# adapter_rev1_tt.net
KiCad netlist of a schematic drawn in Altium Designer
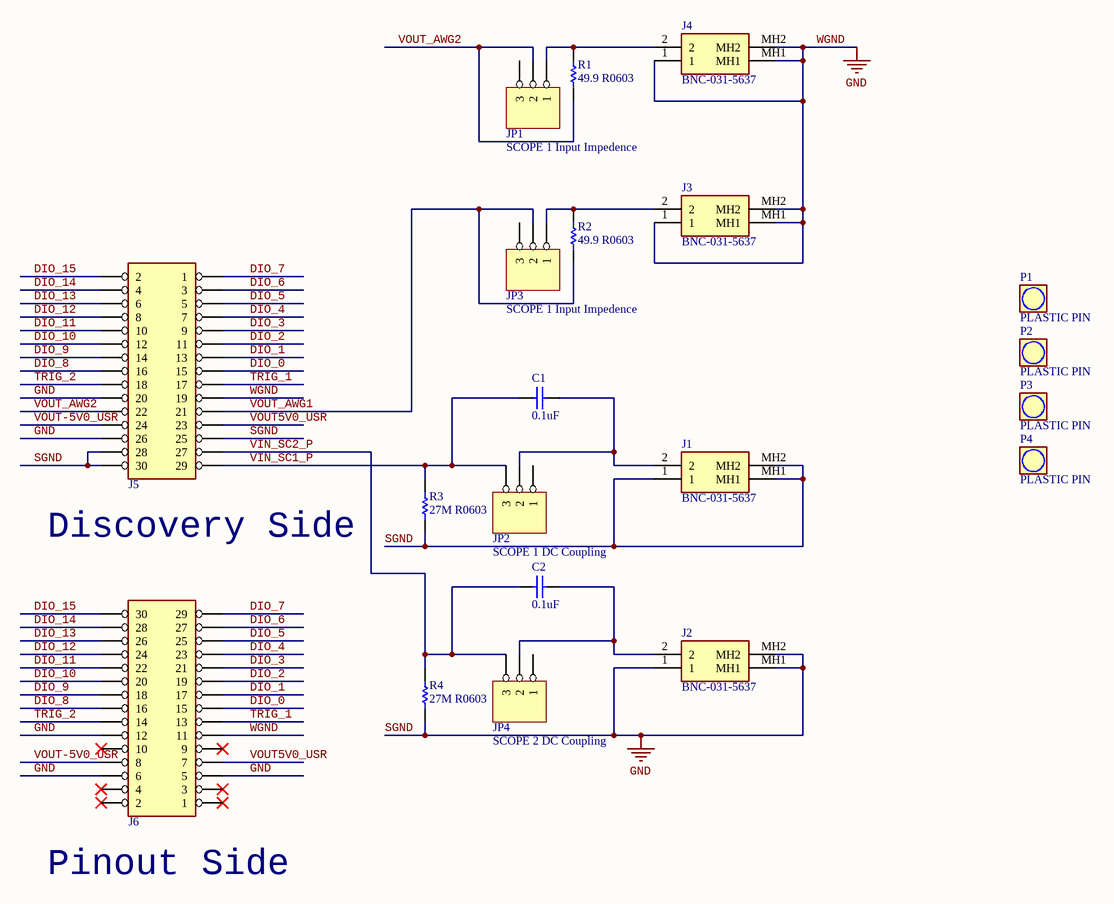
[diagram p0: adapter_rev1_tt.SchDoc]

(export (version "E")
  (design (tool "Eeschema 10.0.6"))
  (components
    (comp (ref "C1")
      (value "0.1uF")
      (footprint "0603_C")
      (description "Capacitor")
      (fields (field (name "PUBLISHER") "Altium Limited"))
      (libsource (lib "My Footprint") (part "CAP"))
    )
    (comp (ref "C2")
      (value "0.1uF")
      (footprint "0603_C")
      (description "Capacitor")
      (fields (field (name "PUBLISHER") "Altium Limited"))
      (libsource (lib "My Footprint") (part "CAP"))
    )
    (comp (ref "J1")
      (value "BNC-031-5637")
      (footprint "0315637")
      (description "Connector")
      (fields
        (field (name "MANUFACTURER_PART_NUMBER") "031-5637")
        (field (name "MOUSER PART NUMBER") "523-31-5637")
      )
      (libsource (lib "My Footprint") (part "BNC-031-5637"))
    )
    (comp (ref "J2")
      (value "BNC-031-5637")
      (footprint "0315637")
      (description "Connector")
      (fields
        (field (name "MANUFACTURER_PART_NUMBER") "031-5637")
        (field (name "MOUSER PART NUMBER") "523-31-5637")
      )
      (libsource (lib "My Footprint") (part "BNC-031-5637"))
    )
    (comp (ref "J3")
      (value "BNC-031-5637")
      (footprint "0315637")
      (description "Connector")
      (fields
        (field (name "MANUFACTURER_PART_NUMBER") "031-5637")
        (field (name "MOUSER PART NUMBER") "523-31-5637")
      )
      (libsource (lib "My Footprint") (part "BNC-031-5637"))
    )
    (comp (ref "J4")
      (value "BNC-031-5637")
      (footprint "0315637")
      (description "Connector")
      (fields
        (field (name "MANUFACTURER_PART_NUMBER") "031-5637")
        (field (name "MOUSER PART NUMBER") "523-31-5637")
      )
      (libsource (lib "My Footprint") (part "BNC-031-5637"))
    )
    (comp (ref "J5")
      (value "HEADER 15x2")
      (footprint "HEADER15X2_CE")
      (libsource (lib "My Footprint") (part "HEADER 15x2"))
    )
    (comp (ref "J6")
      (value "HEADER 15x2")
      (footprint "HEADER15X2_CE")
      (libsource (lib "") (part "HEADER 15x2_1"))
    )
    (comp (ref "JP1")
      (value "SCOPE 1 Input Impedence")
      (footprint "header3")
      (libsource (lib "My Footprint") (part "HEADER 3"))
    )
    (comp (ref "JP2")
      (value "SCOPE 1 DC Coupling")
      (footprint "header3")
      (libsource (lib "My Footprint") (part "HEADER 3"))
    )
    (comp (ref "JP3")
      (value "SCOPE 1 Input Impedence")
      (footprint "header3")
      (libsource (lib "My Footprint") (part "HEADER 3"))
    )
    (comp (ref "JP4")
      (value "SCOPE 2 DC Coupling")
      (footprint "header3")
      (libsource (lib "My Footprint") (part "HEADER 3"))
    )
    (comp (ref "P1")
      (value "PLASTIC PIN")
      (footprint "PLASTIC_PIN")
      (libsource (lib "My Footprint") (part "PLASTIC_PIN"))
    )
    (comp (ref "P2")
      (value "PLASTIC PIN")
      (footprint "PLASTIC_PIN")
      (libsource (lib "My Footprint") (part "PLASTIC_PIN"))
    )
    (comp (ref "P3")
      (value "PLASTIC PIN")
      (footprint "PLASTIC_PIN")
      (libsource (lib "My Footprint") (part "PLASTIC_PIN"))
    )
    (comp (ref "P4")
      (value "PLASTIC PIN")
      (footprint "PLASTIC_PIN")
      (libsource (lib "My Footprint") (part "PLASTIC_PIN"))
    )
    (comp (ref "R1")
      (value "49.9 R0603")
      (footprint "0603_R")
      (description "Resistor")
      (fields (field (name "PUBLISHER") "Altium Limited"))
      (libsource (lib "My Footprint") (part "RES"))
    )
    (comp (ref "R2")
      (value "49.9 R0603")
      (footprint "0603_R")
      (description "Resistor")
      (fields (field (name "PUBLISHER") "Altium Limited"))
      (libsource (lib "My Footprint") (part "RES"))
    )
    (comp (ref "R3")
      (value "27M R0603")
      (footprint "0603_R")
      (description "Resistor")
      (fields (field (name "PUBLISHER") "Altium Limited"))
      (libsource (lib "My Footprint") (part "RES"))
    )
    (comp (ref "R4")
      (value "27M R0603")
      (footprint "0603_R")
      (description "Resistor")
      (fields (field (name "PUBLISHER") "Altium Limited"))
      (libsource (lib "My Footprint") (part "RES"))
    )
  )
  (nets
    (net (code "1") (name "/DIO_0") (class "Default")
      (node (ref "J5") (pin "15") (pinfunction "15_15") (pintype "passive"))
      (node (ref "J6") (pin "15") (pinfunction "15_15") (pintype "passive"))
    )
    (net (code "2") (name "/DIO_1") (class "Default")
      (node (ref "J5") (pin "13") (pinfunction "13_13") (pintype "passive"))
      (node (ref "J6") (pin "17") (pinfunction "17_17") (pintype "passive"))
    )
    (net (code "3") (name "/DIO_2") (class "Default")
      (node (ref "J5") (pin "11") (pinfunction "11_11") (pintype "passive"))
      (node (ref "J6") (pin "19") (pinfunction "19_19") (pintype "passive"))
    )
    (net (code "4") (name "/DIO_3") (class "Default")
      (node (ref "J5") (pin "9") (pinfunction "9_9") (pintype "passive"))
      (node (ref "J6") (pin "21") (pinfunction "21_21") (pintype "passive"))
    )
    (net (code "5") (name "/DIO_4") (class "Default")
      (node (ref "J5") (pin "7") (pinfunction "7_7") (pintype "passive"))
      (node (ref "J6") (pin "23") (pinfunction "23_23") (pintype "passive"))
    )
    (net (code "6") (name "/DIO_5") (class "Default")
      (node (ref "J5") (pin "5") (pinfunction "5_5") (pintype "passive"))
      (node (ref "J6") (pin "25") (pinfunction "25_25") (pintype "passive"))
    )
    (net (code "7") (name "/DIO_6") (class "Default")
      (node (ref "J5") (pin "3") (pinfunction "3_3") (pintype "passive"))
      (node (ref "J6") (pin "27") (pinfunction "27_27") (pintype "passive"))
    )
    (net (code "8") (name "/DIO_7") (class "Default")
      (node (ref "J5") (pin "1") (pinfunction "1_1") (pintype "passive"))
      (node (ref "J6") (pin "29") (pinfunction "29_29") (pintype "passive"))
    )
    (net (code "9") (name "/DIO_8") (class "Default")
      (node (ref "J5") (pin "16") (pinfunction "16_16") (pintype "passive"))
      (node (ref "J6") (pin "16") (pinfunction "16_16") (pintype "passive"))
    )
    (net (code "10") (name "/DIO_9") (class "Default")
      (node (ref "J5") (pin "14") (pinfunction "14_14") (pintype "passive"))
      (node (ref "J6") (pin "18") (pinfunction "18_18") (pintype "passive"))
    )
    (net (code "11") (name "/DIO_10") (class "Default")
      (node (ref "J5") (pin "12") (pinfunction "12_12") (pintype "passive"))
      (node (ref "J6") (pin "20") (pinfunction "20_20") (pintype "passive"))
    )
    (net (code "12") (name "/DIO_11") (class "Default")
      (node (ref "J5") (pin "10") (pinfunction "10_10") (pintype "passive"))
      (node (ref "J6") (pin "22") (pinfunction "22_22") (pintype "passive"))
    )
    (net (code "13") (name "/DIO_12") (class "Default")
      (node (ref "J5") (pin "8") (pinfunction "8_8") (pintype "passive"))
      (node (ref "J6") (pin "24") (pinfunction "24_24") (pintype "passive"))
    )
    (net (code "14") (name "/DIO_13") (class "Default")
      (node (ref "J5") (pin "6") (pinfunction "6_6") (pintype "passive"))
      (node (ref "J6") (pin "26") (pinfunction "26_26") (pintype "passive"))
    )
    (net (code "15") (name "/DIO_14") (class "Default")
      (node (ref "J5") (pin "4") (pinfunction "4_4") (pintype "passive"))
      (node (ref "J6") (pin "28") (pinfunction "28_28") (pintype "passive"))
    )
    (net (code "16") (name "/DIO_15") (class "Default")
      (node (ref "J5") (pin "2") (pinfunction "2_2") (pintype "passive"))
      (node (ref "J6") (pin "30") (pinfunction "30_30") (pintype "passive"))
    )
    (net (code "17") (name "/TRIG_1") (class "Default")
      (node (ref "J5") (pin "17") (pinfunction "17_17") (pintype "passive"))
      (node (ref "J6") (pin "13") (pinfunction "13_13") (pintype "passive"))
    )
    (net (code "18") (name "/TRIG_2") (class "Default")
      (node (ref "J5") (pin "18") (pinfunction "18_18") (pintype "passive"))
      (node (ref "J6") (pin "14") (pinfunction "14_14") (pintype "passive"))
    )
    (net (code "19") (name "/VIN_SC1_P") (class "Default")
      (node (ref "C1") (pin "1") (pinfunction "1_1") (pintype "passive"))
      (node (ref "J5") (pin "29") (pinfunction "29_29") (pintype "passive"))
      (node (ref "JP2") (pin "3") (pinfunction "3_3") (pintype "passive"))
      (node (ref "R3") (pin "2") (pinfunction "2_2") (pintype "passive"))
    )
    (net (code "20") (name "/VIN_SC2_P") (class "Default")
      (node (ref "C2") (pin "1") (pinfunction "1_1") (pintype "passive"))
      (node (ref "J5") (pin "27") (pinfunction "27_27") (pintype "passive"))
      (node (ref "JP4") (pin "3") (pinfunction "3_3") (pintype "passive"))
      (node (ref "R4") (pin "2") (pinfunction "2_2") (pintype "passive"))
    )
    (net (code "21") (name "/VOUT-5V0_USR") (class "Default")
      (node (ref "J5") (pin "24") (pinfunction "24_24") (pintype "passive"))
      (node (ref "J6") (pin "8") (pinfunction "8_8") (pintype "passive"))
    )
    (net (code "22") (name "/VOUT5V0_USR") (class "Default")
      (node (ref "J5") (pin "23") (pinfunction "23_23") (pintype "passive"))
      (node (ref "J6") (pin "7") (pinfunction "7_7") (pintype "passive"))
    )
    (net (code "23") (name "/VOUT_AWG1") (class "Default")
      (node (ref "J5") (pin "21") (pinfunction "21_21") (pintype "passive"))
      (node (ref "JP3") (pin "2") (pinfunction "2_2") (pintype "passive"))
      (node (ref "R2") (pin "2") (pinfunction "2_2") (pintype "passive"))
    )
    (net (code "24") (name "/VOUT_AWG2") (class "Default")
      (node (ref "J5") (pin "22") (pinfunction "22_22") (pintype "passive"))
      (node (ref "JP1") (pin "2") (pinfunction "2_2") (pintype "passive"))
      (node (ref "R1") (pin "2") (pinfunction "2_2") (pintype "passive"))
    )
    (net (code "25") (name "GND") (class "Default")
      (node (ref "J1") (pin "1") (pinfunction "1_1") (pintype "passive"))
      (node (ref "J1") (pin "MH1") (pinfunction "MH1_MH1") (pintype "passive"))
      (node (ref "J1") (pin "MH2") (pinfunction "MH2_MH2") (pintype "passive"))
      (node (ref "J2") (pin "1") (pinfunction "1_1") (pintype "passive"))
      (node (ref "J2") (pin "MH1") (pinfunction "MH1_MH1") (pintype "passive"))
      (node (ref "J2") (pin "MH2") (pinfunction "MH2_MH2") (pintype "passive"))
      (node (ref "J3") (pin "1") (pinfunction "1_1") (pintype "passive"))
      (node (ref "J3") (pin "MH1") (pinfunction "MH1_MH1") (pintype "passive"))
      (node (ref "J3") (pin "MH2") (pinfunction "MH2_MH2") (pintype "passive"))
      (node (ref "J4") (pin "1") (pinfunction "1_1") (pintype "passive"))
      (node (ref "J4") (pin "MH1") (pinfunction "MH1_MH1") (pintype "passive"))
      (node (ref "J4") (pin "MH2") (pinfunction "MH2_MH2") (pintype "passive"))
      (node (ref "J5") (pin "19") (pinfunction "19_19") (pintype "passive"))
      (node (ref "J5") (pin "20") (pinfunction "20_20") (pintype "passive"))
      (node (ref "J5") (pin "25") (pinfunction "25_25") (pintype "passive"))
      (node (ref "J5") (pin "26") (pinfunction "26_26") (pintype "passive"))
      (node (ref "J5") (pin "28") (pinfunction "28_28") (pintype "passive"))
      (node (ref "J5") (pin "30") (pinfunction "30_30") (pintype "passive"))
      (node (ref "J6") (pin "11") (pinfunction "11_11") (pintype "passive"))
      (node (ref "J6") (pin "12") (pinfunction "12_12") (pintype "passive"))
      (node (ref "J6") (pin "5") (pinfunction "5_5") (pintype "passive"))
      (node (ref "J6") (pin "6") (pinfunction "6_6") (pintype "passive"))
      (node (ref "R3") (pin "1") (pinfunction "1_1") (pintype "passive"))
      (node (ref "R4") (pin "1") (pinfunction "1_1") (pintype "passive"))
    )
    (net (code "26") (name "Net-(C1-Pad2)") (class "Default")
      (node (ref "C1") (pin "2") (pinfunction "2_2") (pintype "passive"))
      (node (ref "J1") (pin "2") (pinfunction "2_2") (pintype "passive"))
      (node (ref "JP2") (pin "2") (pinfunction "2_2") (pintype "passive"))
    )
    (net (code "27") (name "Net-(C2-Pad2)") (class "Default")
      (node (ref "C2") (pin "2") (pinfunction "2_2") (pintype "passive"))
      (node (ref "J2") (pin "2") (pinfunction "2_2") (pintype "passive"))
      (node (ref "JP4") (pin "2") (pinfunction "2_2") (pintype "passive"))
    )
    (net (code "28") (name "Net-(J3-Pad2)") (class "Default")
      (node (ref "J3") (pin "2") (pinfunction "2_2") (pintype "passive"))
      (node (ref "JP3") (pin "1") (pinfunction "1_1") (pintype "passive"))
      (node (ref "R2") (pin "1") (pinfunction "1_1") (pintype "passive"))
    )
    (net (code "29") (name "Net-(J4-Pad2)") (class "Default")
      (node (ref "J4") (pin "2") (pinfunction "2_2") (pintype "passive"))
      (node (ref "JP1") (pin "1") (pinfunction "1_1") (pintype "passive"))
      (node (ref "R1") (pin "1") (pinfunction "1_1") (pintype "passive"))
    )
    (net (code "30") (name "unconnected-(J6-Pad1)") (class "Default")
      (node (ref "J6") (pin "1") (pinfunction "1_1") (pintype "passive+no_connect"))
    )
    (net (code "31") (name "unconnected-(J6-Pad2)") (class "Default")
      (node (ref "J6") (pin "2") (pinfunction "2_2") (pintype "passive+no_connect"))
    )
    (net (code "32") (name "unconnected-(J6-Pad3)") (class "Default")
      (node (ref "J6") (pin "3") (pinfunction "3_3") (pintype "passive+no_connect"))
    )
    (net (code "33") (name "unconnected-(J6-Pad4)") (class "Default")
      (node (ref "J6") (pin "4") (pinfunction "4_4") (pintype "passive+no_connect"))
    )
    (net (code "34") (name "unconnected-(J6-Pad9)") (class "Default")
      (node (ref "J6") (pin "9") (pinfunction "9_9") (pintype "passive+no_connect"))
    )
    (net (code "35") (name "unconnected-(J6-Pad10)") (class "Default")
      (node (ref "J6") (pin "10") (pinfunction "10_10") (pintype "passive+no_connect"))
    )
    (net (code "36") (name "unconnected-(JP1-Pad3)") (class "Default")
      (node (ref "JP1") (pin "3") (pinfunction "3_3") (pintype "passive"))
    )
    (net (code "37") (name "unconnected-(JP2-Pad1)") (class "Default")
      (node (ref "JP2") (pin "1") (pinfunction "1_1") (pintype "passive"))
    )
    (net (code "38") (name "unconnected-(JP3-Pad3)") (class "Default")
      (node (ref "JP3") (pin "3") (pinfunction "3_3") (pintype "passive"))
    )
    (net (code "39") (name "unconnected-(JP4-Pad1)") (class "Default")
      (node (ref "JP4") (pin "1") (pinfunction "1_1") (pintype "passive"))
    )
  )
)
